# 07_mPCIe_5-8.net
KiCad netlist of a schematic drawn in Altium Designer
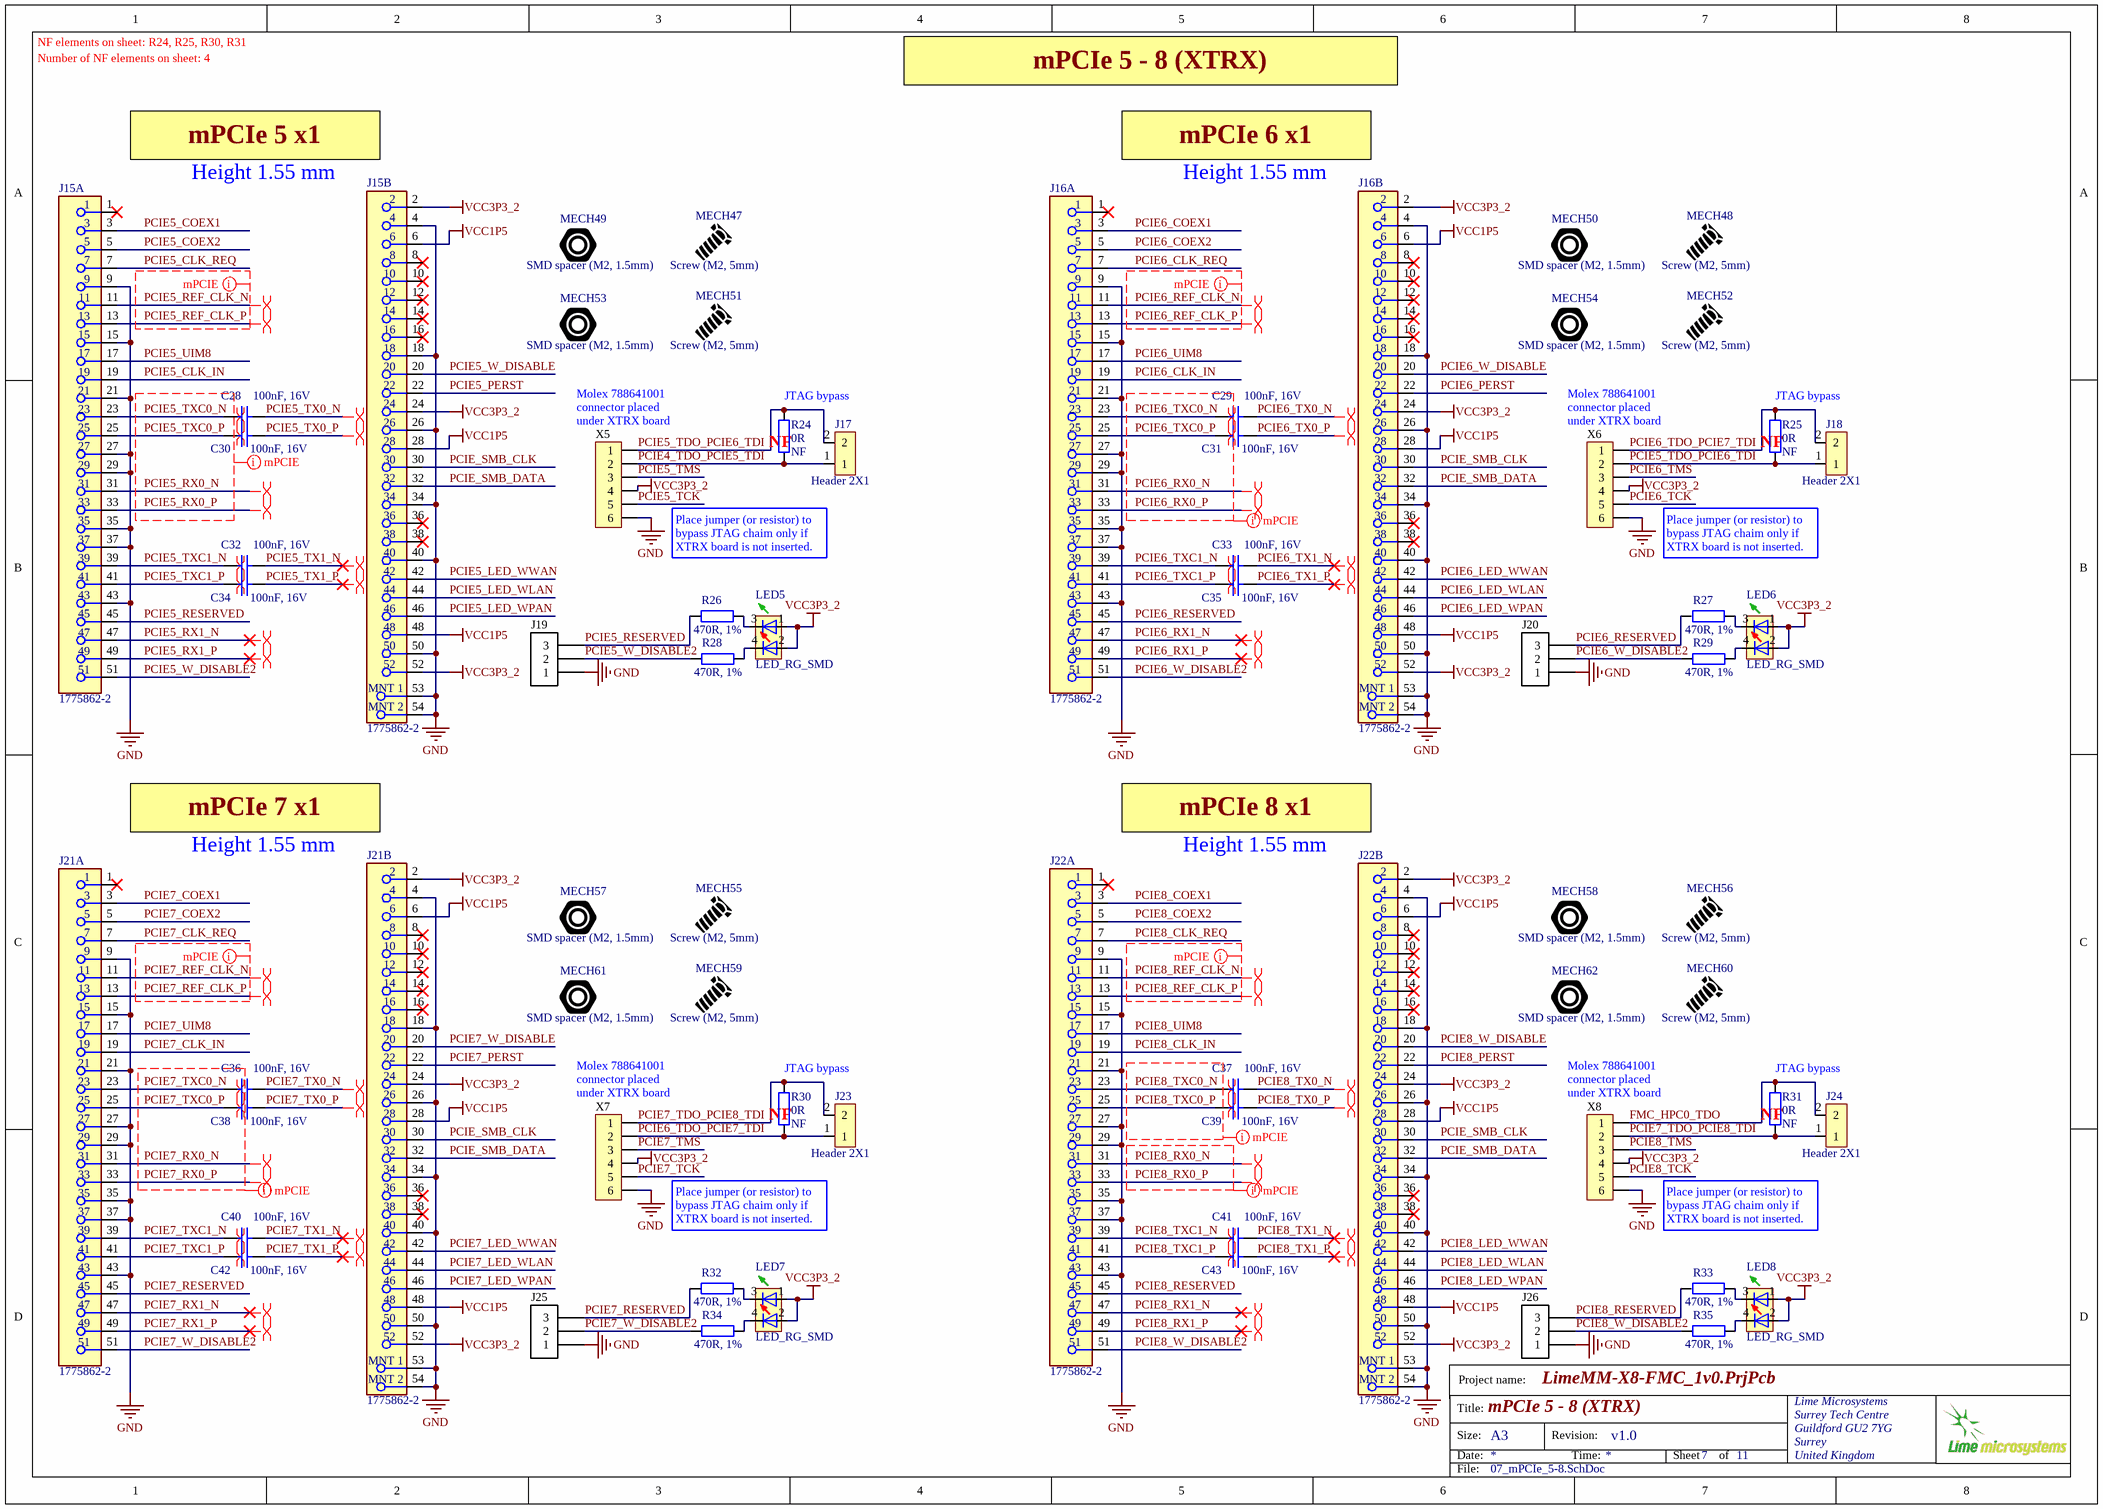
[diagram p0: 07_mPCIe_5-8.SchDoc]

(export (version "E")
  (design (tool "Eeschema 10.0.6"))
  (components
    (comp (ref "C28")
      (value "100nF, 16V")
      (footprint "CAP0402")
      (fields
        (field (name "MANUFACTURER") "Murata Electronics")
        (field (name "TOLERANCE") "10 %")
        (field (name "MANUFACTURER PART NUMBER") "GRM155R71C104KA88D")
      )
      (libsource (lib "LimeMicroAltiumLib_schLib") (part "Cap_0402"))
    )
    (comp (ref "C29")
      (value "100nF, 16V")
      (footprint "CAP0402")
      (fields
        (field (name "MANUFACTURER") "Murata Electronics")
        (field (name "TOLERANCE") "10 %")
        (field (name "MANUFACTURER PART NUMBER") "GRM155R71C104KA88D")
      )
      (libsource (lib "LimeMicroAltiumLib_schLib") (part "Cap_0402"))
    )
    (comp (ref "C30")
      (value "100nF, 16V")
      (footprint "CAP0402")
      (fields
        (field (name "MANUFACTURER") "Murata Electronics")
        (field (name "TOLERANCE") "10 %")
        (field (name "MANUFACTURER PART NUMBER") "GRM155R71C104KA88D")
      )
      (libsource (lib "LimeMicroAltiumLib_schLib") (part "Cap_0402"))
    )
    (comp (ref "C31")
      (value "100nF, 16V")
      (footprint "CAP0402")
      (fields
        (field (name "MANUFACTURER") "Murata Electronics")
        (field (name "TOLERANCE") "10 %")
        (field (name "MANUFACTURER PART NUMBER") "GRM155R71C104KA88D")
      )
      (libsource (lib "LimeMicroAltiumLib_schLib") (part "Cap_0402"))
    )
    (comp (ref "C32")
      (value "100nF, 16V")
      (footprint "CAP0402")
      (fields
        (field (name "MANUFACTURER") "Murata Electronics")
        (field (name "TOLERANCE") "10 %")
        (field (name "MANUFACTURER PART NUMBER") "GRM155R71C104KA88D")
      )
      (libsource (lib "LimeMicroAltiumLib_schLib") (part "Cap_0402"))
    )
    (comp (ref "C33")
      (value "100nF, 16V")
      (footprint "CAP0402")
      (fields
        (field (name "MANUFACTURER") "Murata Electronics")
        (field (name "TOLERANCE") "10 %")
        (field (name "MANUFACTURER PART NUMBER") "GRM155R71C104KA88D")
      )
      (libsource (lib "LimeMicroAltiumLib_schLib") (part "Cap_0402"))
    )
    (comp (ref "C34")
      (value "100nF, 16V")
      (footprint "CAP0402")
      (fields
        (field (name "MANUFACTURER") "Murata Electronics")
        (field (name "TOLERANCE") "10 %")
        (field (name "MANUFACTURER PART NUMBER") "GRM155R71C104KA88D")
      )
      (libsource (lib "LimeMicroAltiumLib_schLib") (part "Cap_0402"))
    )
    (comp (ref "C35")
      (value "100nF, 16V")
      (footprint "CAP0402")
      (fields
        (field (name "MANUFACTURER") "Murata Electronics")
        (field (name "TOLERANCE") "10 %")
        (field (name "MANUFACTURER PART NUMBER") "GRM155R71C104KA88D")
      )
      (libsource (lib "LimeMicroAltiumLib_schLib") (part "Cap_0402"))
    )
    (comp (ref "C36")
      (value "100nF, 16V")
      (footprint "CAP0402")
      (fields
        (field (name "MANUFACTURER") "Murata Electronics")
        (field (name "TOLERANCE") "10 %")
        (field (name "MANUFACTURER PART NUMBER") "GRM155R71C104KA88D")
      )
      (libsource (lib "LimeMicroAltiumLib_schLib") (part "Cap_0402"))
    )
    (comp (ref "C37")
      (value "100nF, 16V")
      (footprint "CAP0402")
      (fields
        (field (name "MANUFACTURER") "Murata Electronics")
        (field (name "TOLERANCE") "10 %")
        (field (name "MANUFACTURER PART NUMBER") "GRM155R71C104KA88D")
      )
      (libsource (lib "LimeMicroAltiumLib_schLib") (part "Cap_0402"))
    )
    (comp (ref "C38")
      (value "100nF, 16V")
      (footprint "CAP0402")
      (fields
        (field (name "MANUFACTURER") "Murata Electronics")
        (field (name "TOLERANCE") "10 %")
        (field (name "MANUFACTURER PART NUMBER") "GRM155R71C104KA88D")
      )
      (libsource (lib "LimeMicroAltiumLib_schLib") (part "Cap_0402"))
    )
    (comp (ref "C39")
      (value "100nF, 16V")
      (footprint "CAP0402")
      (fields
        (field (name "MANUFACTURER") "Murata Electronics")
        (field (name "TOLERANCE") "10 %")
        (field (name "MANUFACTURER PART NUMBER") "GRM155R71C104KA88D")
      )
      (libsource (lib "LimeMicroAltiumLib_schLib") (part "Cap_0402"))
    )
    (comp (ref "C40")
      (value "100nF, 16V")
      (footprint "CAP0402")
      (fields
        (field (name "MANUFACTURER") "Murata Electronics")
        (field (name "TOLERANCE") "10 %")
        (field (name "MANUFACTURER PART NUMBER") "GRM155R71C104KA88D")
      )
      (libsource (lib "LimeMicroAltiumLib_schLib") (part "Cap_0402"))
    )
    (comp (ref "C41")
      (value "100nF, 16V")
      (footprint "CAP0402")
      (fields
        (field (name "MANUFACTURER") "Murata Electronics")
        (field (name "TOLERANCE") "10 %")
        (field (name "MANUFACTURER PART NUMBER") "GRM155R71C104KA88D")
      )
      (libsource (lib "LimeMicroAltiumLib_schLib") (part "Cap_0402"))
    )
    (comp (ref "C42")
      (value "100nF, 16V")
      (footprint "CAP0402")
      (fields
        (field (name "MANUFACTURER") "Murata Electronics")
        (field (name "TOLERANCE") "10 %")
        (field (name "MANUFACTURER PART NUMBER") "GRM155R71C104KA88D")
      )
      (libsource (lib "LimeMicroAltiumLib_schLib") (part "Cap_0402"))
    )
    (comp (ref "C43")
      (value "100nF, 16V")
      (footprint "CAP0402")
      (fields
        (field (name "MANUFACTURER") "Murata Electronics")
        (field (name "TOLERANCE") "10 %")
        (field (name "MANUFACTURER PART NUMBER") "GRM155R71C104KA88D")
      )
      (libsource (lib "LimeMicroAltiumLib_schLib") (part "Cap_0402"))
    )
    (comp (ref "J15")
      (value "1775862-2")
      (footprint "MiniPCIe_connector_XTRX")
      (description "CONN PCI EXP MINI FEMALE 52POS")
      (fields (field (name "MANUFACTURER") "JAE Electronics"))
      (libsource (lib "LimeMicroAltiumLib_schLib_r04") (part "MINI_PCIE_FEMALE"))
    )
    (comp (ref "J16")
      (value "1775862-2")
      (footprint "MiniPCIe_connector_XTRX")
      (description "CONN PCI EXP MINI FEMALE 52POS")
      (fields (field (name "MANUFACTURER") "JAE Electronics"))
      (libsource (lib "LimeMicroAltiumLib_schLib_r04") (part "MINI_PCIE_FEMALE"))
    )
    (comp (ref "J17")
      (value "Header 2X1")
      (footprint "HDR_1x2")
      (fields (field (name "MANUFACTURER") "3M"))
      (libsource (lib "LimeFPGAboard_schLib") (part "Jumper"))
    )
    (comp (ref "J18")
      (value "Header 2X1")
      (footprint "HDR_1x2")
      (fields (field (name "MANUFACTURER") "3M"))
      (libsource (lib "LimeFPGAboard_schLib") (part "Jumper"))
    )
    (comp (ref "J19")
      (value "Header 3x1 pin")
      (footprint "HDR_1x3")
      (description "Header, 3-pin")
      (fields
        (field (name "MANUFACTURER PART NUMBER") "61300311121")
        (field (name "MANUFACTURER") "Wurth Electronics")
      )
      (libsource (lib "LimeMicroAltiumLib_schLib_r04") (part "Header3P"))
    )
    (comp (ref "J20")
      (value "Header 3x1 pin")
      (footprint "HDR_1x3")
      (description "Header, 3-pin")
      (fields
        (field (name "MANUFACTURER PART NUMBER") "61300311121")
        (field (name "MANUFACTURER") "Wurth Electronics")
      )
      (libsource (lib "LimeMicroAltiumLib_schLib_r04") (part "Header3P"))
    )
    (comp (ref "J21")
      (value "1775862-2")
      (footprint "MiniPCIe_connector_XTRX")
      (description "CONN PCI EXP MINI FEMALE 52POS")
      (fields (field (name "MANUFACTURER") "JAE Electronics"))
      (libsource (lib "LimeMicroAltiumLib_schLib_r04") (part "MINI_PCIE_FEMALE"))
    )
    (comp (ref "J22")
      (value "1775862-2")
      (footprint "MiniPCIe_connector_XTRX")
      (description "CONN PCI EXP MINI FEMALE 52POS")
      (fields (field (name "MANUFACTURER") "JAE Electronics"))
      (libsource (lib "LimeMicroAltiumLib_schLib_r04") (part "MINI_PCIE_FEMALE"))
    )
    (comp (ref "J23")
      (value "Header 2X1")
      (footprint "HDR_1x2")
      (fields (field (name "MANUFACTURER") "3M"))
      (libsource (lib "LimeFPGAboard_schLib") (part "Jumper"))
    )
    (comp (ref "J24")
      (value "Header 2X1")
      (footprint "HDR_1x2")
      (fields (field (name "MANUFACTURER") "3M"))
      (libsource (lib "LimeFPGAboard_schLib") (part "Jumper"))
    )
    (comp (ref "J25")
      (value "Header 3x1 pin")
      (footprint "HDR_1x3")
      (description "Header, 3-pin")
      (fields
        (field (name "MANUFACTURER PART NUMBER") "61300311121")
        (field (name "MANUFACTURER") "Wurth Electronics")
      )
      (libsource (lib "LimeMicroAltiumLib_schLib_r04") (part "Header3P"))
    )
    (comp (ref "J26")
      (value "Header 3x1 pin")
      (footprint "HDR_1x3")
      (description "Header, 3-pin")
      (fields
        (field (name "MANUFACTURER PART NUMBER") "61300311121")
        (field (name "MANUFACTURER") "Wurth Electronics")
      )
      (libsource (lib "LimeMicroAltiumLib_schLib_r04") (part "Header3P"))
    )
    (comp (ref "LED5")
      (value "LED_RG_SMD")
      (footprint "LED-2x0603")
      (fields (field (name "MANUFACTURER") "Avago Technologies US Inc."))
      (libsource (lib "LimeMicroAltiumLib_schLib") (part "LED_green_red_SMD"))
    )
    (comp (ref "LED6")
      (value "LED_RG_SMD")
      (footprint "LED-2x0603")
      (fields (field (name "MANUFACTURER") "Avago Technologies US Inc."))
      (libsource (lib "LimeMicroAltiumLib_schLib") (part "LED_green_red_SMD"))
    )
    (comp (ref "LED7")
      (value "LED_RG_SMD")
      (footprint "LED-2x0603")
      (fields (field (name "MANUFACTURER") "Avago Technologies US Inc."))
      (libsource (lib "LimeMicroAltiumLib_schLib") (part "LED_green_red_SMD"))
    )
    (comp (ref "LED8")
      (value "LED_RG_SMD")
      (footprint "LED-2x0603")
      (fields (field (name "MANUFACTURER") "Avago Technologies US Inc."))
      (libsource (lib "LimeMicroAltiumLib_schLib") (part "LED_green_red_SMD"))
    )
    (comp (ref "MECH47")
      (value "Screw (M2, 5mm)")
      (fields (field (name "MANUFACTURER") "B&F Fastener"))
      (libsource (lib "LimeMicroAltiumLib_schLib_r05") (part "Universal_mech_screw"))
    )
    (comp (ref "MECH48")
      (value "Screw (M2, 5mm)")
      (fields (field (name "MANUFACTURER") "B&F Fastener"))
      (libsource (lib "LimeMicroAltiumLib_schLib_r05") (part "Universal_mech_screw"))
    )
    (comp (ref "MECH49")
      (value "SMD spacer (M2, 1.5mm)")
      (fields (field (name "MANUFACTURER") "Wurth Electronics"))
      (libsource (lib "LimeMicroAltiumLib_schLib_r05") (part "Universal_mech_nut"))
    )
    (comp (ref "MECH50")
      (value "SMD spacer (M2, 1.5mm)")
      (fields (field (name "MANUFACTURER") "Wurth Electronics"))
      (libsource (lib "LimeMicroAltiumLib_schLib_r05") (part "Universal_mech_nut"))
    )
    (comp (ref "MECH51")
      (value "Screw (M2, 5mm)")
      (fields (field (name "MANUFACTURER") "B&F Fastener"))
      (libsource (lib "LimeMicroAltiumLib_schLib_r05") (part "Universal_mech_screw"))
    )
    (comp (ref "MECH52")
      (value "Screw (M2, 5mm)")
      (fields (field (name "MANUFACTURER") "B&F Fastener"))
      (libsource (lib "LimeMicroAltiumLib_schLib_r05") (part "Universal_mech_screw"))
    )
    (comp (ref "MECH53")
      (value "SMD spacer (M2, 1.5mm)")
      (fields (field (name "MANUFACTURER") "Wurth Electronics"))
      (libsource (lib "LimeMicroAltiumLib_schLib_r05") (part "Universal_mech_nut"))
    )
    (comp (ref "MECH54")
      (value "SMD spacer (M2, 1.5mm)")
      (fields (field (name "MANUFACTURER") "Wurth Electronics"))
      (libsource (lib "LimeMicroAltiumLib_schLib_r05") (part "Universal_mech_nut"))
    )
    (comp (ref "MECH55")
      (value "Screw (M2, 5mm)")
      (fields (field (name "MANUFACTURER") "B&F Fastener"))
      (libsource (lib "LimeMicroAltiumLib_schLib_r05") (part "Universal_mech_screw"))
    )
    (comp (ref "MECH56")
      (value "Screw (M2, 5mm)")
      (fields (field (name "MANUFACTURER") "B&F Fastener"))
      (libsource (lib "LimeMicroAltiumLib_schLib_r05") (part "Universal_mech_screw"))
    )
    (comp (ref "MECH57")
      (value "SMD spacer (M2, 1.5mm)")
      (fields (field (name "MANUFACTURER") "Wurth Electronics"))
      (libsource (lib "LimeMicroAltiumLib_schLib_r05") (part "Universal_mech_nut"))
    )
    (comp (ref "MECH58")
      (value "SMD spacer (M2, 1.5mm)")
      (fields (field (name "MANUFACTURER") "Wurth Electronics"))
      (libsource (lib "LimeMicroAltiumLib_schLib_r05") (part "Universal_mech_nut"))
    )
    (comp (ref "MECH59")
      (value "Screw (M2, 5mm)")
      (fields (field (name "MANUFACTURER") "B&F Fastener"))
      (libsource (lib "LimeMicroAltiumLib_schLib_r05") (part "Universal_mech_screw"))
    )
    (comp (ref "MECH60")
      (value "Screw (M2, 5mm)")
      (fields (field (name "MANUFACTURER") "B&F Fastener"))
      (libsource (lib "LimeMicroAltiumLib_schLib_r05") (part "Universal_mech_screw"))
    )
    (comp (ref "MECH61")
      (value "SMD spacer (M2, 1.5mm)")
      (fields (field (name "MANUFACTURER") "Wurth Electronics"))
      (libsource (lib "LimeMicroAltiumLib_schLib_r05") (part "Universal_mech_nut"))
    )
    (comp (ref "MECH62")
      (value "SMD spacer (M2, 1.5mm)")
      (fields (field (name "MANUFACTURER") "Wurth Electronics"))
      (libsource (lib "LimeMicroAltiumLib_schLib_r05") (part "Universal_mech_nut"))
    )
    (comp (ref "R24")
      (value "0R")
      (footprint "RES0402")
      (fields
        (field (name "ASSEMBLY INFO") "NF")
        (field (name "MANUFACTURER") "Yageo")
        (field (name "TOLERANCE") "Jumper")
      )
      (libsource (lib "") (part "Res_0402_1"))
    )
    (comp (ref "R25")
      (value "0R")
      (footprint "RES0402")
      (fields
        (field (name "ASSEMBLY INFO") "NF")
        (field (name "MANUFACTURER") "Yageo")
        (field (name "TOLERANCE") "Jumper")
      )
      (libsource (lib "") (part "Res_0402_1"))
    )
    (comp (ref "R26")
      (value "470R, 1%")
      (footprint "RES0402")
      (fields (field (name "TOLERANCE") "1%") (field (name "MANUFACTURER") "Yageo"))
      (libsource (lib "LimeMicroAltiumLib_schLib") (part "Res_0402"))
    )
    (comp (ref "R27")
      (value "470R, 1%")
      (footprint "RES0402")
      (fields (field (name "TOLERANCE") "1%") (field (name "MANUFACTURER") "Yageo"))
      (libsource (lib "LimeMicroAltiumLib_schLib") (part "Res_0402"))
    )
    (comp (ref "R28")
      (value "470R, 1%")
      (footprint "RES0402")
      (fields (field (name "TOLERANCE") "1%") (field (name "MANUFACTURER") "Yageo"))
      (libsource (lib "LimeMicroAltiumLib_schLib") (part "Res_0402"))
    )
    (comp (ref "R29")
      (value "470R, 1%")
      (footprint "RES0402")
      (fields (field (name "TOLERANCE") "1%") (field (name "MANUFACTURER") "Yageo"))
      (libsource (lib "LimeMicroAltiumLib_schLib") (part "Res_0402"))
    )
    (comp (ref "R30")
      (value "0R")
      (footprint "RES0402")
      (fields
        (field (name "ASSEMBLY INFO") "NF")
        (field (name "MANUFACTURER") "Yageo")
        (field (name "TOLERANCE") "Jumper")
      )
      (libsource (lib "") (part "Res_0402_1"))
    )
    (comp (ref "R31")
      (value "0R")
      (footprint "RES0402")
      (fields
        (field (name "ASSEMBLY INFO") "NF")
        (field (name "MANUFACTURER") "Yageo")
        (field (name "TOLERANCE") "Jumper")
      )
      (libsource (lib "") (part "Res_0402_1"))
    )
    (comp (ref "R32")
      (value "470R, 1%")
      (footprint "RES0402")
      (fields (field (name "TOLERANCE") "1%") (field (name "MANUFACTURER") "Yageo"))
      (libsource (lib "LimeMicroAltiumLib_schLib") (part "Res_0402"))
    )
    (comp (ref "R33")
      (value "470R, 1%")
      (footprint "RES0402")
      (fields (field (name "TOLERANCE") "1%") (field (name "MANUFACTURER") "Yageo"))
      (libsource (lib "LimeMicroAltiumLib_schLib") (part "Res_0402"))
    )
    (comp (ref "R34")
      (value "470R, 1%")
      (footprint "RES0402")
      (fields (field (name "TOLERANCE") "1%") (field (name "MANUFACTURER") "Yageo"))
      (libsource (lib "LimeMicroAltiumLib_schLib") (part "Res_0402"))
    )
    (comp (ref "R35")
      (value "470R, 1%")
      (footprint "RES0402")
      (fields (field (name "TOLERANCE") "1%") (field (name "MANUFACTURER") "Yageo"))
      (libsource (lib "LimeMicroAltiumLib_schLib") (part "Res_0402"))
    )
    (comp (ref "X5")
      (value "Molex 0788641001")
      (footprint "Molex_0788641001_spring_contacts_carrier")
      (description "Header, 6-pin")
      (fields (field (name "MANUFACTURER") "Molex"))
      (libsource (lib "LimeMicroAltiumLib_schLib_r04") (part "Molex_0788641001_spring_contacts"))
    )
    (comp (ref "X6")
      (value "Molex 0788641001")
      (footprint "Molex_0788641001_spring_contacts_carrier")
      (description "Header, 6-pin")
      (fields (field (name "MANUFACTURER") "Molex"))
      (libsource (lib "LimeMicroAltiumLib_schLib_r04") (part "Molex_0788641001_spring_contacts"))
    )
    (comp (ref "X7")
      (value "Molex 0788641001")
      (footprint "Molex_0788641001_spring_contacts_carrier")
      (description "Header, 6-pin")
      (fields (field (name "MANUFACTURER") "Molex"))
      (libsource (lib "LimeMicroAltiumLib_schLib_r04") (part "Molex_0788641001_spring_contacts"))
    )
    (comp (ref "X8")
      (value "Molex 0788641001")
      (footprint "Molex_0788641001_spring_contacts_carrier")
      (description "Header, 6-pin")
      (fields (field (name "MANUFACTURER") "Molex"))
      (libsource (lib "LimeMicroAltiumLib_schLib_r04") (part "Molex_0788641001_spring_contacts"))
    )
  )
  (nets
    (net (code "1") (name "/FMC_HPC0_TDO") (class "Default")
      (node (ref "J24") (pin "2") (pinfunction "2_2") (pintype "passive"))
      (node (ref "R31") (pin "1") (pinfunction "1_1") (pintype "passive"))
      (node (ref "X8") (pin "1") (pinfunction "1_1") (pintype "passive"))
    )
    (net (code "2") (name "/PCIE4_TDO_PCIE5_TDI") (class "Default")
      (node (ref "J17") (pin "1") (pinfunction "1_1") (pintype "passive"))
      (node (ref "R24") (pin "2") (pinfunction "2_2") (pintype "passive"))
      (node (ref "X5") (pin "2") (pinfunction "2_2") (pintype "passive"))
    )
    (net (code "3") (name "/PCIE5_CLK_IN") (class "Default")
      (node (ref "J15") (pin "19") (pinfunction "19_19") (pintype "passive"))
    )
    (net (code "4") (name "/PCIE5_CLK_REQ") (class "Default")
      (node (ref "J15") (pin "7") (pinfunction "7_7") (pintype "passive"))
    )
    (net (code "5") (name "/PCIE5_COEX1") (class "Default")
      (node (ref "J15") (pin "3") (pinfunction "3_3") (pintype "passive"))
    )
    (net (code "6") (name "/PCIE5_COEX2") (class "Default")
      (node (ref "J15") (pin "5") (pinfunction "5_5") (pintype "passive"))
    )
    (net (code "7") (name "/PCIE5_LED_WLAN") (class "Default")
      (node (ref "J15") (pin "44") (pinfunction "44_44") (pintype "passive"))
    )
    (net (code "8") (name "/PCIE5_LED_WPAN") (class "Default")
      (node (ref "J15") (pin "46") (pinfunction "46_46") (pintype "passive"))
    )
    (net (code "9") (name "/PCIE5_LED_WWAN") (class "Default")
      (node (ref "J15") (pin "42") (pinfunction "42_42") (pintype "passive"))
    )
    (net (code "10") (name "/PCIE5_PERST") (class "Default")
      (node (ref "J15") (pin "22") (pinfunction "22_22") (pintype "passive"))
    )
    (net (code "11") (name "/PCIE5_REF_CLK_N") (class "Default")
      (node (ref "J15") (pin "11") (pinfunction "11_11") (pintype "passive"))
    )
    (net (code "12") (name "/PCIE5_REF_CLK_P") (class "Default")
      (node (ref "J15") (pin "13") (pinfunction "13_13") (pintype "passive"))
    )
    (net (code "13") (name "/PCIE5_RESERVED") (class "Default")
      (node (ref "J15") (pin "45") (pinfunction "45_45") (pintype "passive"))
      (node (ref "J19") (pin "3") (pinfunction "3_3") (pintype "passive"))
      (node (ref "R26") (pin "2") (pinfunction "2_2") (pintype "passive"))
    )
    (net (code "14") (name "/PCIE5_RX0_N") (class "Default")
      (node (ref "J15") (pin "31") (pinfunction "31_31") (pintype "passive"))
    )
    (net (code "15") (name "/PCIE5_RX0_P") (class "Default")
      (node (ref "J15") (pin "33") (pinfunction "33_33") (pintype "passive"))
    )
    (net (code "16") (name "/PCIE5_RX1_N") (class "Default")
      (node (ref "J15") (pin "47") (pinfunction "47_47") (pintype "passive+no_connect"))
    )
    (net (code "17") (name "/PCIE5_RX1_P") (class "Default")
      (node (ref "J15") (pin "49") (pinfunction "49_49") (pintype "passive+no_connect"))
    )
    (net (code "18") (name "/PCIE5_TCK") (class "Default")
      (node (ref "X5") (pin "5") (pinfunction "5_5") (pintype "passive"))
    )
    (net (code "19") (name "/PCIE5_TDO_PCIE6_TDI") (class "Default")
      (node (ref "J17") (pin "2") (pinfunction "2_2") (pintype "passive"))
      (node (ref "J18") (pin "1") (pinfunction "1_1") (pintype "passive"))
      (node (ref "R24") (pin "1") (pinfunction "1_1") (pintype "passive"))
      (node (ref "R25") (pin "2") (pinfunction "2_2") (pintype "passive"))
      (node (ref "X5") (pin "1") (pinfunction "1_1") (pintype "passive"))
      (node (ref "X6") (pin "2") (pinfunction "2_2") (pintype "passive"))
    )
    (net (code "20") (name "/PCIE5_TMS") (class "Default")
      (node (ref "X5") (pin "3") (pinfunction "3_3") (pintype "passive"))
    )
    (net (code "21") (name "/PCIE5_TX0_N") (class "Default")
      (node (ref "C28") (pin "1") (pinfunction "1_1") (pintype "passive"))
    )
    (net (code "22") (name "/PCIE5_TX0_P") (class "Default")
      (node (ref "C30") (pin "1") (pinfunction "1_1") (pintype "passive"))
    )
    (net (code "23") (name "/PCIE5_TX1_N") (class "Default")
      (node (ref "C32") (pin "1") (pinfunction "1_1") (pintype "passive+no_connect"))
    )
    (net (code "24") (name "/PCIE5_TX1_P") (class "Default")
      (node (ref "C34") (pin "1") (pinfunction "1_1") (pintype "passive+no_connect"))
    )
    (net (code "25") (name "/PCIE5_TXC0_N") (class "Default")
      (node (ref "C28") (pin "2") (pinfunction "2_2") (pintype "passive"))
      (node (ref "J15") (pin "23") (pinfunction "23_23") (pintype "passive"))
    )
    (net (code "26") (name "/PCIE5_TXC0_P") (class "Default")
      (node (ref "C30") (pin "2") (pinfunction "2_2") (pintype "passive"))
      (node (ref "J15") (pin "25") (pinfunction "25_25") (pintype "passive"))
    )
    (net (code "27") (name "/PCIE5_TXC1_N") (class "Default")
      (node (ref "C32") (pin "2") (pinfunction "2_2") (pintype "passive"))
      (node (ref "J15") (pin "39") (pinfunction "39_39") (pintype "passive"))
    )
    (net (code "28") (name "/PCIE5_TXC1_P") (class "Default")
      (node (ref "C34") (pin "2") (pinfunction "2_2") (pintype "passive"))
      (node (ref "J15") (pin "41") (pinfunction "41_41") (pintype "passive"))
    )
    (net (code "29") (name "/PCIE5_UIM8") (class "Default")
      (node (ref "J15") (pin "17") (pinfunction "17_17") (pintype "passive"))
    )
    (net (code "30") (name "/PCIE5_W_DISABLE") (class "Default")
      (node (ref "J15") (pin "20") (pinfunction "20_20") (pintype "passive"))
    )
    (net (code "31") (name "/PCIE5_W_DISABLE2") (class "Default")
      (node (ref "J15") (pin "51") (pinfunction "51_51") (pintype "passive"))
      (node (ref "J19") (pin "2") (pinfunction "2_2") (pintype "passive"))
      (node (ref "R28") (pin "2") (pinfunction "2_2") (pintype "passive"))
    )
    (net (code "32") (name "/PCIE6_CLK_IN") (class "Default")
      (node (ref "J16") (pin "19") (pinfunction "19_19") (pintype "passive"))
    )
    (net (code "33") (name "/PCIE6_CLK_REQ") (class "Default")
      (node (ref "J16") (pin "7") (pinfunction "7_7") (pintype "passive"))
    )
    (net (code "34") (name "/PCIE6_COEX1") (class "Default")
      (node (ref "J16") (pin "3") (pinfunction "3_3") (pintype "passive"))
    )
    (net (code "35") (name "/PCIE6_COEX2") (class "Default")
      (node (ref "J16") (pin "5") (pinfunction "5_5") (pintype "passive"))
    )
    (net (code "36") (name "/PCIE6_LED_WLAN") (class "Default")
      (node (ref "J16") (pin "44") (pinfunction "44_44") (pintype "passive"))
    )
    (net (code "37") (name "/PCIE6_LED_WPAN") (class "Default")
      (node (ref "J16") (pin "46") (pinfunction "46_46") (pintype "passive"))
    )
    (net (code "38") (name "/PCIE6_LED_WWAN") (class "Default")
      (node (ref "J16") (pin "42") (pinfunction "42_42") (pintype "passive"))
    )
    (net (code "39") (name "/PCIE6_PERST") (class "Default")
      (node (ref "J16") (pin "22") (pinfunction "22_22") (pintype "passive"))
    )
    (net (code "40") (name "/PCIE6_REF_CLK_N") (class "Default")
      (node (ref "J16") (pin "11") (pinfunction "11_11") (pintype "passive"))
    )
    (net (code "41") (name "/PCIE6_REF_CLK_P") (class "Default")
      (node (ref "J16") (pin "13") (pinfunction "13_13") (pintype "passive"))
    )
    (net (code "42") (name "/PCIE6_RESERVED") (class "Default")
      (node (ref "J16") (pin "45") (pinfunction "45_45") (pintype "passive"))
      (node (ref "J20") (pin "3") (pinfunction "3_3") (pintype "passive"))
      (node (ref "R27") (pin "2") (pinfunction "2_2") (pintype "passive"))
    )
    (net (code "43") (name "/PCIE6_RX0_N") (class "Default")
      (node (ref "J16") (pin "31") (pinfunction "31_31") (pintype "passive"))
    )
    (net (code "44") (name "/PCIE6_RX0_P") (class "Default")
      (node (ref "J16") (pin "33") (pinfunction "33_33") (pintype "passive"))
    )
    (net (code "45") (name "/PCIE6_RX1_N") (class "Default")
      (node (ref "J16") (pin "47") (pinfunction "47_47") (pintype "passive+no_connect"))
    )
    (net (code "46") (name "/PCIE6_RX1_P") (class "Default")
      (node (ref "J16") (pin "49") (pinfunction "49_49") (pintype "passive+no_connect"))
    )
    (net (code "47") (name "/PCIE6_TCK") (class "Default")
      (node (ref "X6") (pin "5") (pinfunction "5_5") (pintype "passive"))
    )
    (net (code "48") (name "/PCIE6_TDO_PCIE7_TDI") (class "Default")
      (node (ref "J18") (pin "2") (pinfunction "2_2") (pintype "passive"))
      (node (ref "J23") (pin "1") (pinfunction "1_1") (pintype "passive"))
      (node (ref "R25") (pin "1") (pinfunction "1_1") (pintype "passive"))
      (node (ref "R30") (pin "2") (pinfunction "2_2") (pintype "passive"))
      (node (ref "X6") (pin "1") (pinfunction "1_1") (pintype "passive"))
      (node (ref "X7") (pin "2") (pinfunction "2_2") (pintype "passive"))
    )
    (net (code "49") (name "/PCIE6_TMS") (class "Default")
      (node (ref "X6") (pin "3") (pinfunction "3_3") (pintype "passive"))
    )
    (net (code "50") (name "/PCIE6_TX0_N") (class "Default")
      (node (ref "C29") (pin "1") (pinfunction "1_1") (pintype "passive"))
    )
    (net (code "51") (name "/PCIE6_TX0_P") (class "Default")
      (node (ref "C31") (pin "1") (pinfunction "1_1") (pintype "passive"))
    )
    (net (code "52") (name "/PCIE6_TX1_N") (class "Default")
      (node (ref "C33") (pin "1") (pinfunction "1_1") (pintype "passive+no_connect"))
    )
    (net (code "53") (name "/PCIE6_TX1_P") (class "Default")
      (node (ref "C35") (pin "1") (pinfunction "1_1") (pintype "passive+no_connect"))
    )
    (net (code "54") (name "/PCIE6_TXC0_N") (class "Default")
      (node (ref "C29") (pin "2") (pinfunction "2_2") (pintype "passive"))
      (node (ref "J16") (pin "23") (pinfunction "23_23") (pintype "passive"))
    )
    (net (code "55") (name "/PCIE6_TXC0_P") (class "Default")
      (node (ref "C31") (pin "2") (pinfunction "2_2") (pintype "passive"))
      (node (ref "J16") (pin "25") (pinfunction "25_25") (pintype "passive"))
    )
    (net (code "56") (name "/PCIE6_TXC1_N") (class "Default")
      (node (ref "C33") (pin "2") (pinfunction "2_2") (pintype "passive"))
      (node (ref "J16") (pin "39") (pinfunction "39_39") (pintype "passive"))
    )
    (net (code "57") (name "/PCIE6_TXC1_P") (class "Default")
      (node (ref "C35") (pin "2") (pinfunction "2_2") (pintype "passive"))
      (node (ref "J16") (pin "41") (pinfunction "41_41") (pintype "passive"))
    )
    (net (code "58") (name "/PCIE6_UIM8") (class "Default")
      (node (ref "J16") (pin "17") (pinfunction "17_17") (pintype "passive"))
    )
    (net (code "59") (name "/PCIE6_W_DISABLE") (class "Default")
      (node (ref "J16") (pin "20") (pinfunction "20_20") (pintype "passive"))
    )
    (net (code "60") (name "/PCIE6_W_DISABLE2") (class "Default")
      (node (ref "J16") (pin "51") (pinfunction "51_51") (pintype "passive"))
      (node (ref "J20") (pin "2") (pinfunction "2_2") (pintype "passive"))
      (node (ref "R29") (pin "2") (pinfunction "2_2") (pintype "passive"))
    )
    (net (code "61") (name "/PCIE7_CLK_IN") (class "Default")
      (node (ref "J21") (pin "19") (pinfunction "19_19") (pintype "passive"))
    )
    (net (code "62") (name "/PCIE7_CLK_REQ") (class "Default")
      (node (ref "J21") (pin "7") (pinfunction "7_7") (pintype "passive"))
    )
    (net (code "63") (name "/PCIE7_COEX1") (class "Default")
      (node (ref "J21") (pin "3") (pinfunction "3_3") (pintype "passive"))
    )
    (net (code "64") (name "/PCIE7_COEX2") (class "Default")
      (node (ref "J21") (pin "5") (pinfunction "5_5") (pintype "passive"))
    )
    (net (code "65") (name "/PCIE7_LED_WLAN") (class "Default")
      (node (ref "J21") (pin "44") (pinfunction "44_44") (pintype "passive"))
    )
    (net (code "66") (name "/PCIE7_LED_WPAN") (class "Default")
      (node (ref "J21") (pin "46") (pinfunction "46_46") (pintype "passive"))
    )
    (net (code "67") (name "/PCIE7_LED_WWAN") (class "Default")
      (node (ref "J21") (pin "42") (pinfunction "42_42") (pintype "passive"))
    )
    (net (code "68") (name "/PCIE7_PERST") (class "Default")
      (node (ref "J21") (pin "22") (pinfunction "22_22") (pintype "passive"))
    )
    (net (code "69") (name "/PCIE7_REF_CLK_N") (class "Default")
      (node (ref "J21") (pin "11") (pinfunction "11_11") (pintype "passive"))
    )
    (net (code "70") (name "/PCIE7_REF_CLK_P") (class "Default")
      (node (ref "J21") (pin "13") (pinfunction "13_13") (pintype "passive"))
    )
    (net (code "71") (name "/PCIE7_RESERVED") (class "Default")
      (node (ref "J21") (pin "45") (pinfunction "45_45") (pintype "passive"))
      (node (ref "J25") (pin "3") (pinfunction "3_3") (pintype "passive"))
      (node (ref "R32") (pin "2") (pinfunction "2_2") (pintype "passive"))
    )
    (net (code "72") (name "/PCIE7_RX0_N") (class "Default")
      (node (ref "J21") (pin "31") (pinfunction "31_31") (pintype "passive"))
    )
    (net (code "73") (name "/PCIE7_RX0_P") (class "Default")
      (node (ref "J21") (pin "33") (pinfunction "33_33") (pintype "passive"))
    )
    (net (code "74") (name "/PCIE7_RX1_N") (class "Default")
      (node (ref "J21") (pin "47") (pinfunction "47_47") (pintype "passive+no_connect"))
    )
    (net (code "75") (name "/PCIE7_RX1_P") (class "Default")
      (node (ref "J21") (pin "49") (pinfunction "49_49") (pintype "passive+no_connect"))
    )
    (net (code "76") (name "/PCIE7_TCK") (class "Default")
      (node (ref "X7") (pin "5") (pinfunction "5_5") (pintype "passive"))
    )
    (net (code "77") (name "/PCIE7_TDO_PCIE8_TDI") (class "Default")
      (node (ref "J23") (pin "2") (pinfunction "2_2") (pintype "passive"))
      (node (ref "J24") (pin "1") (pinfunction "1_1") (pintype "passive"))
      (node (ref "R30") (pin "1") (pinfunction "1_1") (pintype "passive"))
      (node (ref "R31") (pin "2") (pinfunction "2_2") (pintype "passive"))
      (node (ref "X7") (pin "1") (pinfunction "1_1") (pintype "passive"))
      (node (ref "X8") (pin "2") (pinfunction "2_2") (pintype "passive"))
    )
    (net (code "78") (name "/PCIE7_TMS") (class "Default")
      (node (ref "X7") (pin "3") (pinfunction "3_3") (pintype "passive"))
    )
    (net (code "79") (name "/PCIE7_TX0_N") (class "Default")
      (node (ref "C36") (pin "1") (pinfunction "1_1") (pintype "passive"))
    )
    (net (code "80") (name "/PCIE7_TX0_P") (class "Default")
      (node (ref "C38") (pin "1") (pinfunction "1_1") (pintype "passive"))
    )
    (net (code "81") (name "/PCIE7_TX1_N") (class "Default")
      (node (ref "C40") (pin "1") (pinfunction "1_1") (pintype "passive+no_connect"))
    )
    (net (code "82") (name "/PCIE7_TX1_P") (class "Default")
      (node (ref "C42") (pin "1") (pinfunction "1_1") (pintype "passive+no_connect"))
    )
    (net (code "83") (name "/PCIE7_TXC0_N") (class "Default")
      (node (ref "C36") (pin "2") (pinfunction "2_2") (pintype "passive"))
      (node (ref "J21") (pin "23") (pinfunction "23_23") (pintype "passive"))
    )
    (net (code "84") (name "/PCIE7_TXC0_P") (class "Default")
      (node (ref "C38") (pin "2") (pinfunction "2_2") (pintype "passive"))
      (node (ref "J21") (pin "25") (pinfunction "25_25") (pintype "passive"))
    )
    (net (code "85") (name "/PCIE7_TXC1_N") (class "Default")
      (node (ref "C40") (pin "2") (pinfunction "2_2") (pintype "passive"))
      (node (ref "J21") (pin "39") (pinfunction "39_39") (pintype "passive"))
    )
    (net (code "86") (name "/PCIE7_TXC1_P") (class "Default")
      (node (ref "C42") (pin "2") (pinfunction "2_2") (pintype "passive"))
      (node (ref "J21") (pin "41") (pinfunction "41_41") (pintype "passive"))
    )
    (net (code "87") (name "/PCIE7_UIM8") (class "Default")
      (node (ref "J21") (pin "17") (pinfunction "17_17") (pintype "passive"))
    )
    (net (code "88") (name "/PCIE7_W_DISABLE") (class "Default")
      (node (ref "J21") (pin "20") (pinfunction "20_20") (pintype "passive"))
    )
    (net (code "89") (name "/PCIE7_W_DISABLE2") (class "Default")
      (node (ref "J21") (pin "51") (pinfunction "51_51") (pintype "passive"))
      (node (ref "J25") (pin "2") (pinfunction "2_2") (pintype "passive"))
      (node (ref "R34") (pin "2") (pinfunction "2_2") (pintype "passive"))
    )
    (net (code "90") (name "/PCIE8_CLK_IN") (class "Default")
      (node (ref "J22") (pin "19") (pinfunction "19_19") (pintype "passive"))
    )
    (net (code "91") (name "/PCIE8_CLK_REQ") (class "Default")
      (node (ref "J22") (pin "7") (pinfunction "7_7") (pintype "passive"))
    )
    (net (code "92") (name "/PCIE8_COEX1") (class "Default")
      (node (ref "J22") (pin "3") (pinfunction "3_3") (pintype "passive"))
    )
    (net (code "93") (name "/PCIE8_COEX2") (class "Default")
      (node (ref "J22") (pin "5") (pinfunction "5_5") (pintype "passive"))
    )
    (net (code "94") (name "/PCIE8_LED_WLAN") (class "Default")
      (node (ref "J22") (pin "44") (pinfunction "44_44") (pintype "passive"))
    )
    (net (code "95") (name "/PCIE8_LED_WPAN") (class "Default")
      (node (ref "J22") (pin "46") (pinfunction "46_46") (pintype "passive"))
    )
    (net (code "96") (name "/PCIE8_LED_WWAN") (class "Default")
      (node (ref "J22") (pin "42") (pinfunction "42_42") (pintype "passive"))
    )
    (net (code "97") (name "/PCIE8_PERST") (class "Default")
      (node (ref "J22") (pin "22") (pinfunction "22_22") (pintype "passive"))
    )
    (net (code "98") (name "/PCIE8_REF_CLK_N") (class "Default")
      (node (ref "J22") (pin "11") (pinfunction "11_11") (pintype "passive"))
    )
    (net (code "99") (name "/PCIE8_REF_CLK_P") (class "Default")
      (node (ref "J22") (pin "13") (pinfunction "13_13") (pintype "passive"))
    )
    (net (code "100") (name "/PCIE8_RESERVED") (class "Default")
      (node (ref "J22") (pin "45") (pinfunction "45_45") (pintype "passive"))
      (node (ref "J26") (pin "3") (pinfunction "3_3") (pintype "passive"))
      (node (ref "R33") (pin "2") (pinfunction "2_2") (pintype "passive"))
    )
    (net (code "101") (name "/PCIE8_RX0_N") (class "Default")
      (node (ref "J22") (pin "31") (pinfunction "31_31") (pintype "passive"))
    )
    (net (code "102") (name "/PCIE8_RX0_P") (class "Default")
      (node (ref "J22") (pin "33") (pinfunction "33_33") (pintype "passive"))
    )
    (net (code "103") (name "/PCIE8_RX1_N") (class "Default")
      (node (ref "J22") (pin "47") (pinfunction "47_47") (pintype "passive+no_connect"))
    )
    (net (code "104") (name "/PCIE8_RX1_P") (class "Default")
      (node (ref "J22") (pin "49") (pinfunction "49_49") (pintype "passive+no_connect"))
    )
    (net (code "105") (name "/PCIE8_TCK") (class "Default")
      (node (ref "X8") (pin "5") (pinfunction "5_5") (pintype "passive"))
    )
    (net (code "106") (name "/PCIE8_TMS") (class "Default")
      (node (ref "X8") (pin "3") (pinfunction "3_3") (pintype "passive"))
    )
    (net (code "107") (name "/PCIE8_TX0_N") (class "Default")
      (node (ref "C37") (pin "1") (pinfunction "1_1") (pintype "passive"))
    )
    (net (code "108") (name "/PCIE8_TX0_P") (class "Default")
      (node (ref "C39") (pin "1") (pinfunction "1_1") (pintype "passive"))
    )
    (net (code "109") (name "/PCIE8_TX1_N") (class "Default")
      (node (ref "C41") (pin "1") (pinfunction "1_1") (pintype "passive+no_connect"))
    )
    (net (code "110") (name "/PCIE8_TX1_P") (class "Default")
      (node (ref "C43") (pin "1") (pinfunction "1_1") (pintype "passive+no_connect"))
    )
    (net (code "111") (name "/PCIE8_TXC0_N") (class "Default")
      (node (ref "C37") (pin "2") (pinfunction "2_2") (pintype "passive"))
      (node (ref "J22") (pin "23") (pinfunction "23_23") (pintype "passive"))
    )
    (net (code "112") (name "/PCIE8_TXC0_P") (class "Default")
      (node (ref "C39") (pin "2") (pinfunction "2_2") (pintype "passive"))
      (node (ref "J22") (pin "25") (pinfunction "25_25") (pintype "passive"))
    )
    (net (code "113") (name "/PCIE8_TXC1_N") (class "Default")
      (node (ref "C41") (pin "2") (pinfunction "2_2") (pintype "passive"))
      (node (ref "J22") (pin "39") (pinfunction "39_39") (pintype "passive"))
    )
    (net (code "114") (name "/PCIE8_TXC1_P") (class "Default")
      (node (ref "C43") (pin "2") (pinfunction "2_2") (pintype "passive"))
      (node (ref "J22") (pin "41") (pinfunction "41_41") (pintype "passive"))
    )
    (net (code "115") (name "/PCIE8_UIM8") (class "Default")
      (node (ref "J22") (pin "17") (pinfunction "17_17") (pintype "passive"))
    )
    (net (code "116") (name "/PCIE8_W_DISABLE") (class "Default")
      (node (ref "J22") (pin "20") (pinfunction "20_20") (pintype "passive"))
    )
    (net (code "117") (name "/PCIE8_W_DISABLE2") (class "Default")
      (node (ref "J22") (pin "51") (pinfunction "51_51") (pintype "passive"))
      (node (ref "J26") (pin "2") (pinfunction "2_2") (pintype "passive"))
      (node (ref "R35") (pin "2") (pinfunction "2_2") (pintype "passive"))
    )
    (net (code "118") (name "/PCIE_SMB_CLK") (class "Default")
      (node (ref "J15") (pin "30") (pinfunction "30_30") (pintype "passive"))
      (node (ref "J16") (pin "30") (pinfunction "30_30") (pintype "passive"))
      (node (ref "J21") (pin "30") (pinfunction "30_30") (pintype "passive"))
      (node (ref "J22") (pin "30") (pinfunction "30_30") (pintype "passive"))
    )
    (net (code "119") (name "/PCIE_SMB_DATA") (class "Default")
      (node (ref "J15") (pin "32") (pinfunction "32_32") (pintype "passive"))
      (node (ref "J16") (pin "32") (pinfunction "32_32") (pintype "passive"))
      (node (ref "J21") (pin "32") (pinfunction "32_32") (pintype "passive"))
      (node (ref "J22") (pin "32") (pinfunction "32_32") (pintype "passive"))
    )
    (net (code "120") (name "GND") (class "Default")
      (node (ref "J15") (pin "15") (pinfunction "15_15") (pintype "passive"))
      (node (ref "J15") (pin "18") (pinfunction "18_18") (pintype "passive"))
      (node (ref "J15") (pin "21") (pinfunction "21_21") (pintype "passive"))
      (node (ref "J15") (pin "26") (pinfunction "26_26") (pintype "passive"))
      (node (ref "J15") (pin "27") (pinfunction "27_27") (pintype "passive"))
      (node (ref "J15") (pin "29") (pinfunction "29_29") (pintype "passive"))
      (node (ref "J15") (pin "34") (pinfunction "34_34") (pintype "passive"))
      (node (ref "J15") (pin "35") (pinfunction "35_35") (pintype "passive"))
      (node (ref "J15") (pin "37") (pinfunction "37_37") (pintype "passive"))
      (node (ref "J15") (pin "4") (pinfunction "4_4") (pintype "passive"))
      (node (ref "J15") (pin "40") (pinfunction "40_40") (pintype "passive"))
      (node (ref "J15") (pin "43") (pinfunction "43_43") (pintype "passive"))
      (node (ref "J15") (pin "50") (pinfunction "50_50") (pintype "passive"))
      (node (ref "J15") (pin "53") (pinfunction "MNT_1_53") (pintype "passive"))
      (node (ref "J15") (pin "54") (pinfunction "MNT_2_54") (pintype "passive"))
      (node (ref "J15") (pin "9") (pinfunction "9_9") (pintype "passive"))
      (node (ref "J16") (pin "15") (pinfunction "15_15") (pintype "passive"))
      (node (ref "J16") (pin "18") (pinfunction "18_18") (pintype "passive"))
      (node (ref "J16") (pin "21") (pinfunction "21_21") (pintype "passive"))
      (node (ref "J16") (pin "26") (pinfunction "26_26") (pintype "passive"))
      (node (ref "J16") (pin "27") (pinfunction "27_27") (pintype "passive"))
      (node (ref "J16") (pin "29") (pinfunction "29_29") (pintype "passive"))
      (node (ref "J16") (pin "34") (pinfunction "34_34") (pintype "passive"))
      (node (ref "J16") (pin "35") (pinfunction "35_35") (pintype "passive"))
      (node (ref "J16") (pin "37") (pinfunction "37_37") (pintype "passive"))
      (node (ref "J16") (pin "4") (pinfunction "4_4") (pintype "passive"))
      (node (ref "J16") (pin "40") (pinfunction "40_40") (pintype "passive"))
      (node (ref "J16") (pin "43") (pinfunction "43_43") (pintype "passive"))
      (node (ref "J16") (pin "50") (pinfunction "50_50") (pintype "passive"))
      (node (ref "J16") (pin "53") (pinfunction "MNT_1_53") (pintype "passive"))
      (node (ref "J16") (pin "54") (pinfunction "MNT_2_54") (pintype "passive"))
      (node (ref "J16") (pin "9") (pinfunction "9_9") (pintype "passive"))
      (node (ref "J19") (pin "1") (pinfunction "1_1") (pintype "passive"))
      (node (ref "J20") (pin "1") (pinfunction "1_1") (pintype "passive"))
      (node (ref "J21") (pin "15") (pinfunction "15_15") (pintype "passive"))
      (node (ref "J21") (pin "18") (pinfunction "18_18") (pintype "passive"))
      (node (ref "J21") (pin "21") (pinfunction "21_21") (pintype "passive"))
      (node (ref "J21") (pin "26") (pinfunction "26_26") (pintype "passive"))
      (node (ref "J21") (pin "27") (pinfunction "27_27") (pintype "passive"))
      (node (ref "J21") (pin "29") (pinfunction "29_29") (pintype "passive"))
      (node (ref "J21") (pin "34") (pinfunction "34_34") (pintype "passive"))
      (node (ref "J21") (pin "35") (pinfunction "35_35") (pintype "passive"))
      (node (ref "J21") (pin "37") (pinfunction "37_37") (pintype "passive"))
      (node (ref "J21") (pin "4") (pinfunction "4_4") (pintype "passive"))
      (node (ref "J21") (pin "40") (pinfunction "40_40") (pintype "passive"))
      (node (ref "J21") (pin "43") (pinfunction "43_43") (pintype "passive"))
      (node (ref "J21") (pin "50") (pinfunction "50_50") (pintype "passive"))
      (node (ref "J21") (pin "53") (pinfunction "MNT_1_53") (pintype "passive"))
      (node (ref "J21") (pin "54") (pinfunction "MNT_2_54") (pintype "passive"))
      (node (ref "J21") (pin "9") (pinfunction "9_9") (pintype "passive"))
      (node (ref "J22") (pin "15") (pinfunction "15_15") (pintype "passive"))
      (node (ref "J22") (pin "18") (pinfunction "18_18") (pintype "passive"))
      (node (ref "J22") (pin "21") (pinfunction "21_21") (pintype "passive"))
      (node (ref "J22") (pin "26") (pinfunction "26_26") (pintype "passive"))
      (node (ref "J22") (pin "27") (pinfunction "27_27") (pintype "passive"))
      (node (ref "J22") (pin "29") (pinfunction "29_29") (pintype "passive"))
      (node (ref "J22") (pin "34") (pinfunction "34_34") (pintype "passive"))
      (node (ref "J22") (pin "35") (pinfunction "35_35") (pintype "passive"))
      (node (ref "J22") (pin "37") (pinfunction "37_37") (pintype "passive"))
      (node (ref "J22") (pin "4") (pinfunction "4_4") (pintype "passive"))
      (node (ref "J22") (pin "40") (pinfunction "40_40") (pintype "passive"))
      (node (ref "J22") (pin "43") (pinfunction "43_43") (pintype "passive"))
      (node (ref "J22") (pin "50") (pinfunction "50_50") (pintype "passive"))
      (node (ref "J22") (pin "53") (pinfunction "MNT_1_53") (pintype "passive"))
      (node (ref "J22") (pin "54") (pinfunction "MNT_2_54") (pintype "passive"))
      (node (ref "J22") (pin "9") (pinfunction "9_9") (pintype "passive"))
      (node (ref "J25") (pin "1") (pinfunction "1_1") (pintype "passive"))
      (node (ref "J26") (pin "1") (pinfunction "1_1") (pintype "passive"))
      (node (ref "X5") (pin "6") (pinfunction "6_6") (pintype "passive"))
      (node (ref "X6") (pin "6") (pinfunction "6_6") (pintype "passive"))
      (node (ref "X7") (pin "6") (pinfunction "6_6") (pintype "passive"))
      (node (ref "X8") (pin "6") (pinfunction "6_6") (pintype "passive"))
    )
    (net (code "121") (name "Net-(LED5-Pad3)") (class "Default")
      (node (ref "LED5") (pin "3") (pinfunction "3_3") (pintype "power_in"))
      (node (ref "R26") (pin "1") (pinfunction "1_1") (pintype "passive"))
    )
    (net (code "122") (name "Net-(LED5-Pad4)") (class "Default")
      (node (ref "LED5") (pin "4") (pinfunction "4_4") (pintype "power_in"))
      (node (ref "R28") (pin "1") (pinfunction "1_1") (pintype "passive"))
    )
    (net (code "123") (name "Net-(LED6-Pad3)") (class "Default")
      (node (ref "LED6") (pin "3") (pinfunction "3_3") (pintype "power_in"))
      (node (ref "R27") (pin "1") (pinfunction "1_1") (pintype "passive"))
    )
    (net (code "124") (name "Net-(LED6-Pad4)") (class "Default")
      (node (ref "LED6") (pin "4") (pinfunction "4_4") (pintype "power_in"))
      (node (ref "R29") (pin "1") (pinfunction "1_1") (pintype "passive"))
    )
    (net (code "125") (name "Net-(LED7-Pad3)") (class "Default")
      (node (ref "LED7") (pin "3") (pinfunction "3_3") (pintype "power_in"))
      (node (ref "R32") (pin "1") (pinfunction "1_1") (pintype "passive"))
    )
    (net (code "126") (name "Net-(LED7-Pad4)") (class "Default")
      (node (ref "LED7") (pin "4") (pinfunction "4_4") (pintype "power_in"))
      (node (ref "R34") (pin "1") (pinfunction "1_1") (pintype "passive"))
    )
    (net (code "127") (name "Net-(LED8-Pad3)") (class "Default")
      (node (ref "LED8") (pin "3") (pinfunction "3_3") (pintype "power_in"))
      (node (ref "R33") (pin "1") (pinfunction "1_1") (pintype "passive"))
    )
    (net (code "128") (name "Net-(LED8-Pad4)") (class "Default")
      (node (ref "LED8") (pin "4") (pinfunction "4_4") (pintype "power_in"))
      (node (ref "R35") (pin "1") (pinfunction "1_1") (pintype "passive"))
    )
    (net (code "129") (name "VCC1P5") (class "Default")
      (node (ref "J15") (pin "28") (pinfunction "28_28") (pintype "passive"))
      (node (ref "J15") (pin "48") (pinfunction "48_48") (pintype "passive"))
      (node (ref "J15") (pin "6") (pinfunction "6_6") (pintype "passive"))
      (node (ref "J16") (pin "28") (pinfunction "28_28") (pintype "passive"))
      (node (ref "J16") (pin "48") (pinfunction "48_48") (pintype "passive"))
      (node (ref "J16") (pin "6") (pinfunction "6_6") (pintype "passive"))
      (node (ref "J21") (pin "28") (pinfunction "28_28") (pintype "passive"))
      (node (ref "J21") (pin "48") (pinfunction "48_48") (pintype "passive"))
      (node (ref "J21") (pin "6") (pinfunction "6_6") (pintype "passive"))
      (node (ref "J22") (pin "28") (pinfunction "28_28") (pintype "passive"))
      (node (ref "J22") (pin "48") (pinfunction "48_48") (pintype "passive"))
      (node (ref "J22") (pin "6") (pinfunction "6_6") (pintype "passive"))
    )
    (net (code "130") (name "VCC3P3_2") (class "Default")
      (node (ref "J15") (pin "2") (pinfunction "2_2") (pintype "passive"))
      (node (ref "J15") (pin "24") (pinfunction "24_24") (pintype "passive"))
      (node (ref "J15") (pin "52") (pinfunction "52_52") (pintype "passive"))
      (node (ref "J16") (pin "2") (pinfunction "2_2") (pintype "passive"))
      (node (ref "J16") (pin "24") (pinfunction "24_24") (pintype "passive"))
      (node (ref "J16") (pin "52") (pinfunction "52_52") (pintype "passive"))
      (node (ref "J21") (pin "2") (pinfunction "2_2") (pintype "passive"))
      (node (ref "J21") (pin "24") (pinfunction "24_24") (pintype "passive"))
      (node (ref "J21") (pin "52") (pinfunction "52_52") (pintype "passive"))
      (node (ref "J22") (pin "2") (pinfunction "2_2") (pintype "passive"))
      (node (ref "J22") (pin "24") (pinfunction "24_24") (pintype "passive"))
      (node (ref "J22") (pin "52") (pinfunction "52_52") (pintype "passive"))
      (node (ref "LED5") (pin "1") (pinfunction "1_1") (pintype "power_in"))
      (node (ref "LED5") (pin "2") (pinfunction "2_2") (pintype "power_in"))
      (node (ref "LED6") (pin "1") (pinfunction "1_1") (pintype "power_in"))
      (node (ref "LED6") (pin "2") (pinfunction "2_2") (pintype "power_in"))
      (node (ref "LED7") (pin "1") (pinfunction "1_1") (pintype "power_in"))
      (node (ref "LED7") (pin "2") (pinfunction "2_2") (pintype "power_in"))
      (node (ref "LED8") (pin "1") (pinfunction "1_1") (pintype "power_in"))
      (node (ref "LED8") (pin "2") (pinfunction "2_2") (pintype "power_in"))
      (node (ref "X5") (pin "4") (pinfunction "4_4") (pintype "passive"))
      (node (ref "X6") (pin "4") (pinfunction "4_4") (pintype "passive"))
      (node (ref "X7") (pin "4") (pinfunction "4_4") (pintype "passive"))
      (node (ref "X8") (pin "4") (pinfunction "4_4") (pintype "passive"))
    )
    (net (code "131") (name "unconnected-(J15-Pad1)") (class "Default")
      (node (ref "J15") (pin "1") (pinfunction "1_1") (pintype "passive+no_connect"))
    )
    (net (code "132") (name "unconnected-(J15-Pad8)") (class "Default")
      (node (ref "J15") (pin "8") (pinfunction "8_8") (pintype "passive+no_connect"))
    )
    (net (code "133") (name "unconnected-(J15-Pad10)") (class "Default")
      (node (ref "J15") (pin "10") (pinfunction "10_10") (pintype "passive+no_connect"))
    )
    (net (code "134") (name "unconnected-(J15-Pad12)") (class "Default")
      (node (ref "J15") (pin "12") (pinfunction "12_12") (pintype "passive+no_connect"))
    )
    (net (code "135") (name "unconnected-(J15-Pad14)") (class "Default")
      (node (ref "J15") (pin "14") (pinfunction "14_14") (pintype "passive+no_connect"))
    )
    (net (code "136") (name "unconnected-(J15-Pad16)") (class "Default")
      (node (ref "J15") (pin "16") (pinfunction "16_16") (pintype "passive+no_connect"))
    )
    (net (code "137") (name "unconnected-(J15-Pad36)") (class "Default")
      (node (ref "J15") (pin "36") (pinfunction "36_36") (pintype "passive+no_connect"))
    )
    (net (code "138") (name "unconnected-(J15-Pad38)") (class "Default")
      (node (ref "J15") (pin "38") (pinfunction "38_38") (pintype "passive+no_connect"))
    )
    (net (code "139") (name "unconnected-(J16-Pad1)") (class "Default")
      (node (ref "J16") (pin "1") (pinfunction "1_1") (pintype "passive+no_connect"))
    )
    (net (code "140") (name "unconnected-(J16-Pad8)") (class "Default")
      (node (ref "J16") (pin "8") (pinfunction "8_8") (pintype "passive+no_connect"))
    )
    (net (code "141") (name "unconnected-(J16-Pad10)") (class "Default")
      (node (ref "J16") (pin "10") (pinfunction "10_10") (pintype "passive+no_connect"))
    )
    (net (code "142") (name "unconnected-(J16-Pad12)") (class "Default")
      (node (ref "J16") (pin "12") (pinfunction "12_12") (pintype "passive+no_connect"))
    )
    (net (code "143") (name "unconnected-(J16-Pad14)") (class "Default")
      (node (ref "J16") (pin "14") (pinfunction "14_14") (pintype "passive+no_connect"))
    )
    (net (code "144") (name "unconnected-(J16-Pad16)") (class "Default")
      (node (ref "J16") (pin "16") (pinfunction "16_16") (pintype "passive+no_connect"))
    )
    (net (code "145") (name "unconnected-(J16-Pad36)") (class "Default")
      (node (ref "J16") (pin "36") (pinfunction "36_36") (pintype "passive+no_connect"))
    )
    (net (code "146") (name "unconnected-(J16-Pad38)") (class "Default")
      (node (ref "J16") (pin "38") (pinfunction "38_38") (pintype "passive+no_connect"))
    )
    (net (code "147") (name "unconnected-(J21-Pad1)") (class "Default")
      (node (ref "J21") (pin "1") (pinfunction "1_1") (pintype "passive+no_connect"))
    )
    (net (code "148") (name "unconnected-(J21-Pad8)") (class "Default")
      (node (ref "J21") (pin "8") (pinfunction "8_8") (pintype "passive+no_connect"))
    )
    (net (code "149") (name "unconnected-(J21-Pad10)") (class "Default")
      (node (ref "J21") (pin "10") (pinfunction "10_10") (pintype "passive+no_connect"))
    )
    (net (code "150") (name "unconnected-(J21-Pad12)") (class "Default")
      (node (ref "J21") (pin "12") (pinfunction "12_12") (pintype "passive+no_connect"))
    )
    (net (code "151") (name "unconnected-(J21-Pad14)") (class "Default")
      (node (ref "J21") (pin "14") (pinfunction "14_14") (pintype "passive+no_connect"))
    )
    (net (code "152") (name "unconnected-(J21-Pad16)") (class "Default")
      (node (ref "J21") (pin "16") (pinfunction "16_16") (pintype "passive+no_connect"))
    )
    (net (code "153") (name "unconnected-(J21-Pad36)") (class "Default")
      (node (ref "J21") (pin "36") (pinfunction "36_36") (pintype "passive+no_connect"))
    )
    (net (code "154") (name "unconnected-(J21-Pad38)") (class "Default")
      (node (ref "J21") (pin "38") (pinfunction "38_38") (pintype "passive+no_connect"))
    )
    (net (code "155") (name "unconnected-(J22-Pad1)") (class "Default")
      (node (ref "J22") (pin "1") (pinfunction "1_1") (pintype "passive+no_connect"))
    )
    (net (code "156") (name "unconnected-(J22-Pad8)") (class "Default")
      (node (ref "J22") (pin "8") (pinfunction "8_8") (pintype "passive+no_connect"))
    )
    (net (code "157") (name "unconnected-(J22-Pad10)") (class "Default")
      (node (ref "J22") (pin "10") (pinfunction "10_10") (pintype "passive+no_connect"))
    )
    (net (code "158") (name "unconnected-(J22-Pad12)") (class "Default")
      (node (ref "J22") (pin "12") (pinfunction "12_12") (pintype "passive+no_connect"))
    )
    (net (code "159") (name "unconnected-(J22-Pad14)") (class "Default")
      (node (ref "J22") (pin "14") (pinfunction "14_14") (pintype "passive+no_connect"))
    )
    (net (code "160") (name "unconnected-(J22-Pad16)") (class "Default")
      (node (ref "J22") (pin "16") (pinfunction "16_16") (pintype "passive+no_connect"))
    )
    (net (code "161") (name "unconnected-(J22-Pad36)") (class "Default")
      (node (ref "J22") (pin "36") (pinfunction "36_36") (pintype "passive+no_connect"))
    )
    (net (code "162") (name "unconnected-(J22-Pad38)") (class "Default")
      (node (ref "J22") (pin "38") (pinfunction "38_38") (pintype "passive+no_connect"))
    )
  )
)
